# DCDC-17VXV5A.net
KiCad netlist of a schematic drawn in EAGLE
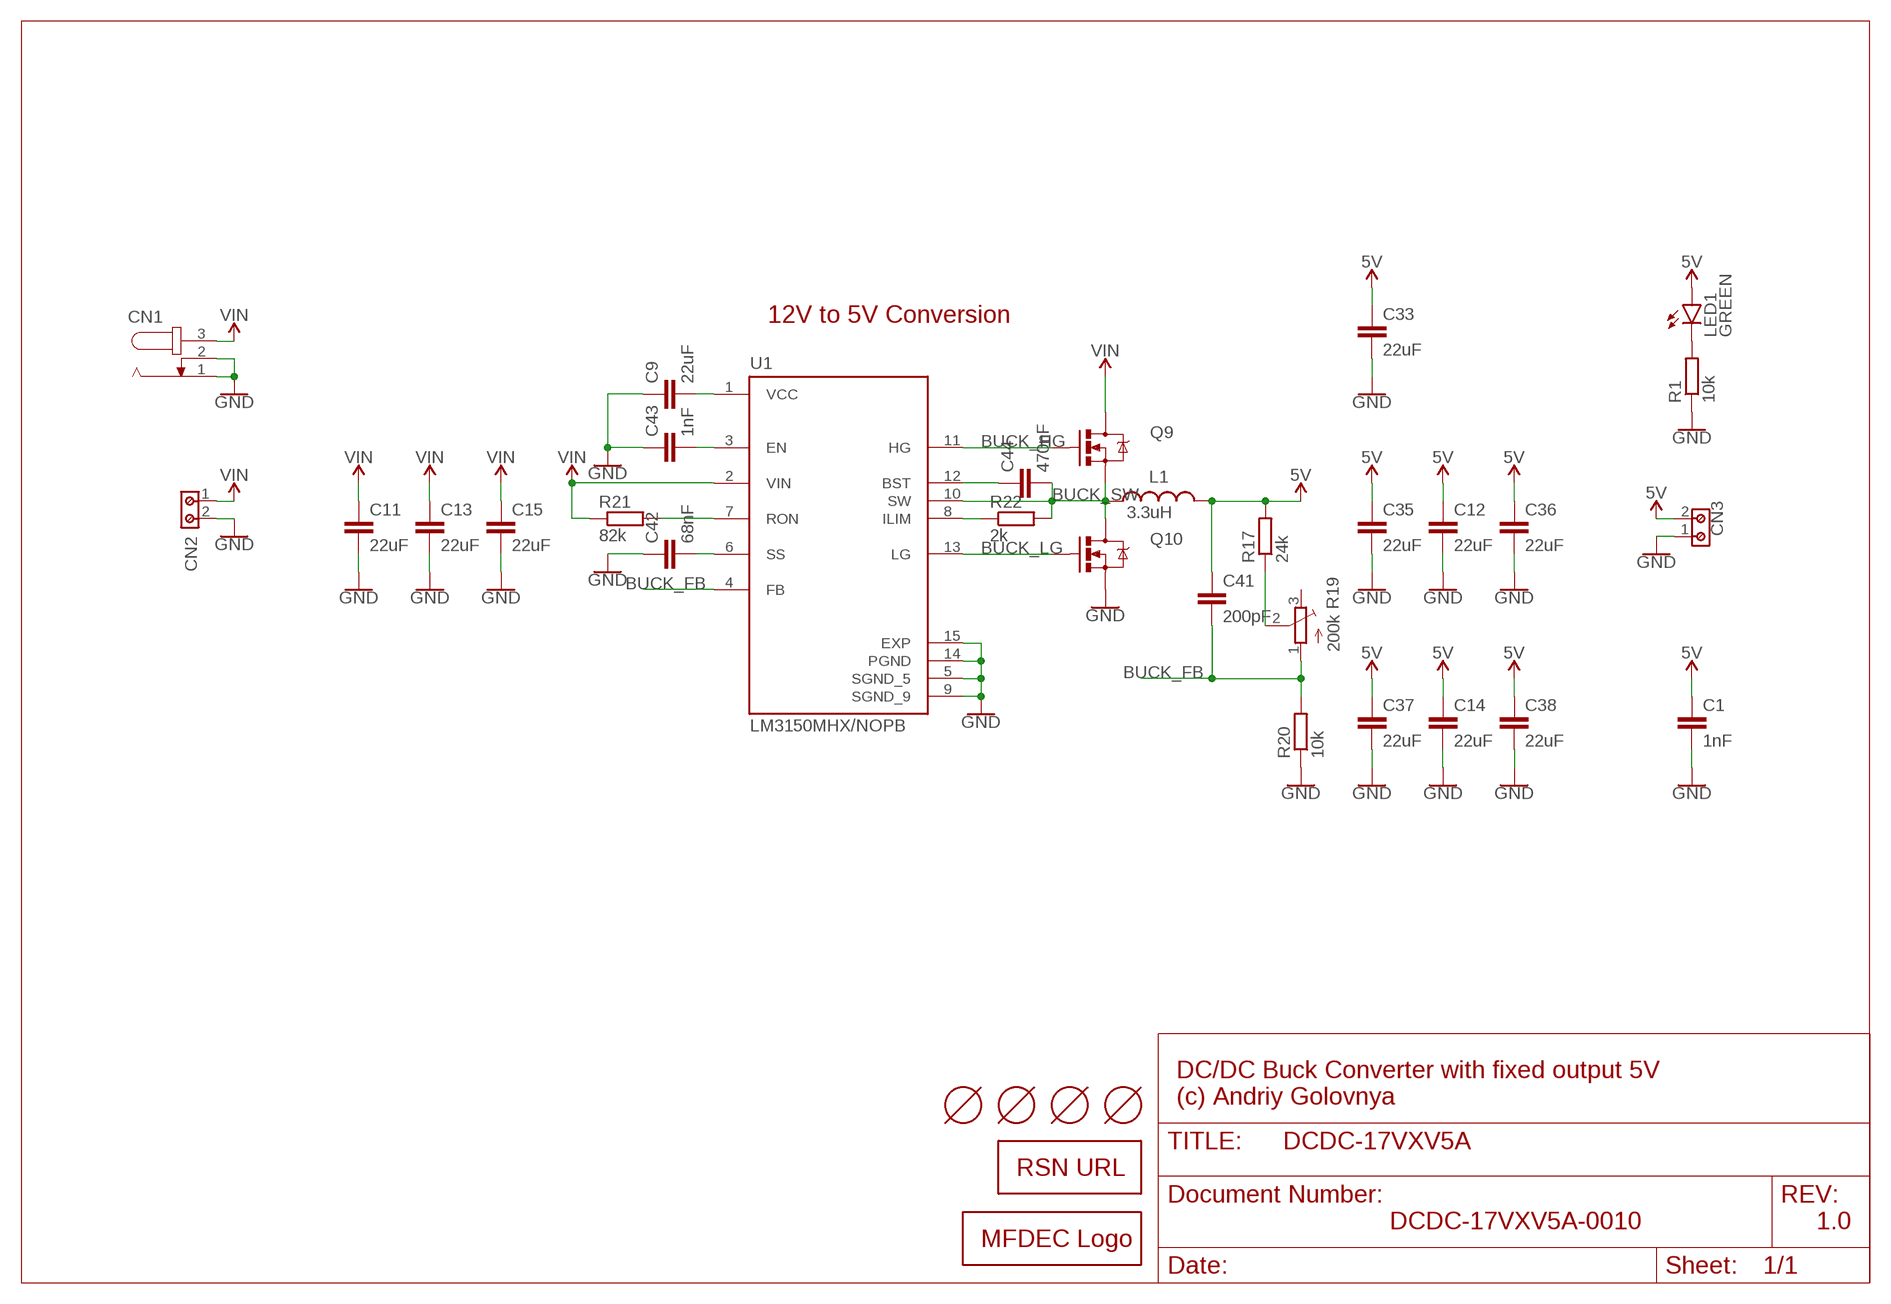
[diagram p0: schematic, sheet 1]

(export (version "E")
  (design (tool "Eeschema 10.0.6"))
  (components
    (comp (ref "C1")
      (value "1nF")
      (footprint "eagle-import:C0603K")
      (libsource (lib "eagle-import") (part "C-EUC0603K"))
    )
    (comp (ref "C9")
      (value "22uF")
      (footprint "eagle-import:C0805K")
      (libsource (lib "eagle-import") (part "C-EUC0805K"))
    )
    (comp (ref "C11")
      (value "22uF")
      (footprint "eagle-import:C0805K")
      (libsource (lib "eagle-import") (part "C-EUC0805K"))
    )
    (comp (ref "C12")
      (value "22uF")
      (footprint "eagle-import:C0805K")
      (libsource (lib "eagle-import") (part "C-EUC0805K"))
    )
    (comp (ref "C13")
      (value "22uF")
      (footprint "eagle-import:C0805K")
      (libsource (lib "eagle-import") (part "C-EUC0805K"))
    )
    (comp (ref "C14")
      (value "22uF")
      (footprint "eagle-import:C0805K")
      (libsource (lib "eagle-import") (part "C-EUC0805K"))
    )
    (comp (ref "C15")
      (value "22uF")
      (footprint "eagle-import:C0805K")
      (libsource (lib "eagle-import") (part "C-EUC0805K"))
    )
    (comp (ref "C33")
      (value "22uF")
      (footprint "eagle-import:C0805K")
      (libsource (lib "eagle-import") (part "C-EUC0805K"))
    )
    (comp (ref "C35")
      (value "22uF")
      (footprint "eagle-import:C0805K")
      (libsource (lib "eagle-import") (part "C-EUC0805K"))
    )
    (comp (ref "C36")
      (value "22uF")
      (footprint "eagle-import:C0805K")
      (libsource (lib "eagle-import") (part "C-EUC0805K"))
    )
    (comp (ref "C37")
      (value "22uF")
      (footprint "eagle-import:C0805K")
      (libsource (lib "eagle-import") (part "C-EUC0805K"))
    )
    (comp (ref "C38")
      (value "22uF")
      (footprint "eagle-import:C0805K")
      (libsource (lib "eagle-import") (part "C-EUC0805K"))
    )
    (comp (ref "C41")
      (value "200pF")
      (footprint "eagle-import:C0603K")
      (libsource (lib "eagle-import") (part "C-EUC0603K"))
    )
    (comp (ref "C42")
      (value "68nF")
      (footprint "eagle-import:C0603K")
      (libsource (lib "eagle-import") (part "C-EUC0603K"))
    )
    (comp (ref "C43")
      (value "1nF")
      (footprint "eagle-import:C0603K")
      (libsource (lib "eagle-import") (part "C-EUC0603K"))
    )
    (comp (ref "C44")
      (value "470nF")
      (footprint "eagle-import:C0603K")
      (libsource (lib "eagle-import") (part "C-EUC0603K"))
    )
    (comp (ref "CN1")
      (value "JACK-PLUG1")
      (footprint "eagle-import:SPC4078")
      (libsource (lib "eagle-import") (part "JACK-PLUG1"))
    )
    (comp (ref "CN2")
      (value "691213510002")
      (footprint "eagle-import:691213510002")
      (libsource (lib "eagle-import") (part "691213510002"))
    )
    (comp (ref "CN3")
      (value "691213510002")
      (footprint "eagle-import:691213510002")
      (libsource (lib "eagle-import") (part "691213510002"))
    )
    (comp (ref "HOLE1")
      (value "TOOLINGHOLE")
      (footprint "eagle-import:TOOLING-HOLE")
      (libsource (lib "eagle-import") (part "TOOLINGHOLE"))
    )
    (comp (ref "HOLE2")
      (value "TOOLINGHOLE")
      (footprint "eagle-import:TOOLING-HOLE")
      (libsource (lib "eagle-import") (part "TOOLINGHOLE"))
    )
    (comp (ref "HOLE3")
      (value "TOOLINGHOLE")
      (footprint "eagle-import:TOOLING-HOLE")
      (libsource (lib "eagle-import") (part "TOOLINGHOLE"))
    )
    (comp (ref "HOLE4")
      (value "TOOLINGHOLE")
      (footprint "eagle-import:TOOLING-HOLE")
      (libsource (lib "eagle-import") (part "TOOLINGHOLE"))
    )
    (comp (ref "L1")
      (value "3.3uH")
      (footprint "eagle-import:WE-CHSA_1011")
      (libsource (lib "eagle-import") (part "WE-CHSA_1011_7843330330"))
    )
    (comp (ref "LED1")
      (value "GREEN")
      (footprint "eagle-import:SML0603")
      (libsource (lib "eagle-import") (part "LEDSML0603"))
    )
    (comp (ref "LOGO1")
      (value "RSNURL_QR_8MM")
      (footprint "eagle-import:RSNURL_QR_8MM")
      (libsource (lib "eagle-import") (part "RSNURL_QR_8MM"))
    )
    (comp (ref "LOGO2")
      (value "MFDECLOGO_L_10MM")
      (footprint "eagle-import:MFDEC_L_10MM")
      (libsource (lib "eagle-import") (part "MFDECLOGO_L_10MM"))
    )
    (comp (ref "Q9")
      (value "NMOSFET")
      (footprint "eagle-import:DPAK")
      (libsource (lib "eagle-import") (part "MOSFET-NCHANNELFDD8780"))
    )
    (comp (ref "Q10")
      (value "NMOSFET")
      (footprint "eagle-import:DPAK")
      (libsource (lib "eagle-import") (part "MOSFET-NCHANNELFDD8780"))
    )
    (comp (ref "R1")
      (value "10k")
      (footprint "eagle-import:R0603")
      (libsource (lib "eagle-import") (part "R-EU_R0603"))
    )
    (comp (ref "R17")
      (value "24k")
      (footprint "eagle-import:R0603")
      (libsource (lib "eagle-import") (part "R-EU_R0603"))
    )
    (comp (ref "R19")
      (value "200k")
      (footprint "eagle-import:TC33X")
      (libsource (lib "eagle-import") (part "TRIMPOTTC33X"))
    )
    (comp (ref "R20")
      (value "10k")
      (footprint "eagle-import:R0603")
      (libsource (lib "eagle-import") (part "R-EU_R0603"))
    )
    (comp (ref "R21")
      (value "82k")
      (footprint "eagle-import:R0603")
      (libsource (lib "eagle-import") (part "R-EU_R0603"))
    )
    (comp (ref "R22")
      (value "2k")
      (footprint "eagle-import:R0603")
      (libsource (lib "eagle-import") (part "R-EU_R0603"))
    )
    (comp (ref "U1")
      (value "LM3150MHX/NOPB")
      (footprint "eagle-import:SOP65P640X110-15N")
      (fields (field (name "MF") "Texas Instruments"))
      (libsource (lib "eagle-import") (part "LM3150MHX/NOPB"))
    )
  )
  (nets
    (net (code "1") (name "/BUCK_FB") (class "Default")
      (node (ref "C41") (pin "2") (pinfunction "2_2") (pintype "passive"))
      (node (ref "R19") (pin "1") (pinfunction "A_1") (pintype "passive"))
      (node (ref "R20") (pin "2") (pinfunction "2_2") (pintype "passive"))
      (node (ref "U1") (pin "4") (pinfunction "FB_4") (pintype "input"))
    )
    (net (code "2") (name "/BUCK_HG") (class "Default")
      (node (ref "Q9") (pin "1") (pinfunction "G_1") (pintype "passive"))
      (node (ref "U1") (pin "11") (pinfunction "HG_11") (pintype "output"))
    )
    (net (code "3") (name "/BUCK_LG") (class "Default")
      (node (ref "Q10") (pin "1") (pinfunction "G_1") (pintype "passive"))
      (node (ref "U1") (pin "13") (pinfunction "LG_13") (pintype "output"))
    )
    (net (code "4") (name "/BUCK_SW") (class "Default")
      (node (ref "C44") (pin "2") (pinfunction "2_2") (pintype "passive"))
      (node (ref "L1") (pin "1") (pinfunction "1_1") (pintype "passive"))
      (node (ref "Q10") (pin "4") (pinfunction "D_4") (pintype "passive"))
      (node (ref "Q9") (pin "3") (pinfunction "S_3") (pintype "passive"))
      (node (ref "R22") (pin "2") (pinfunction "2_2") (pintype "passive"))
      (node (ref "U1") (pin "10") (pinfunction "SW_10") (pintype "output"))
    )
    (net (code "5") (name "5V") (class "Default")
      (node (ref "C1") (pin "1") (pinfunction "1_1") (pintype "passive"))
      (node (ref "C12") (pin "1") (pinfunction "1_1") (pintype "passive"))
      (node (ref "C14") (pin "1") (pinfunction "1_1") (pintype "passive"))
      (node (ref "C33") (pin "1") (pinfunction "1_1") (pintype "passive"))
      (node (ref "C35") (pin "1") (pinfunction "1_1") (pintype "passive"))
      (node (ref "C36") (pin "1") (pinfunction "1_1") (pintype "passive"))
      (node (ref "C37") (pin "1") (pinfunction "1_1") (pintype "passive"))
      (node (ref "C38") (pin "1") (pinfunction "1_1") (pintype "passive"))
      (node (ref "C41") (pin "1") (pinfunction "1_1") (pintype "passive"))
      (node (ref "CN3") (pin "2") (pinfunction "2_2") (pintype "passive"))
      (node (ref "L1") (pin "2") (pinfunction "2_2") (pintype "passive"))
      (node (ref "LED1") (pin "A") (pinfunction "A_A") (pintype "passive"))
      (node (ref "R17") (pin "2") (pinfunction "2_2") (pintype "passive"))
    )
    (net (code "6") (name "GND") (class "Default")
      (node (ref "C1") (pin "2") (pinfunction "2_2") (pintype "passive"))
      (node (ref "C11") (pin "2") (pinfunction "2_2") (pintype "passive"))
      (node (ref "C12") (pin "2") (pinfunction "2_2") (pintype "passive"))
      (node (ref "C13") (pin "2") (pinfunction "2_2") (pintype "passive"))
      (node (ref "C14") (pin "2") (pinfunction "2_2") (pintype "passive"))
      (node (ref "C15") (pin "2") (pinfunction "2_2") (pintype "passive"))
      (node (ref "C33") (pin "2") (pinfunction "2_2") (pintype "passive"))
      (node (ref "C35") (pin "2") (pinfunction "2_2") (pintype "passive"))
      (node (ref "C36") (pin "2") (pinfunction "2_2") (pintype "passive"))
      (node (ref "C37") (pin "2") (pinfunction "2_2") (pintype "passive"))
      (node (ref "C38") (pin "2") (pinfunction "2_2") (pintype "passive"))
      (node (ref "C42") (pin "1") (pinfunction "1_1") (pintype "passive"))
      (node (ref "C43") (pin "1") (pinfunction "1_1") (pintype "passive"))
      (node (ref "C9") (pin "1") (pinfunction "1_1") (pintype "passive"))
      (node (ref "CN1") (pin "1") (pinfunction "1_1") (pintype "passive"))
      (node (ref "CN1") (pin "2") (pinfunction "2_2") (pintype "passive"))
      (node (ref "CN2") (pin "2") (pinfunction "2_2") (pintype "passive"))
      (node (ref "CN3") (pin "1") (pinfunction "1_1") (pintype "passive"))
      (node (ref "Q10") (pin "3") (pinfunction "S_3") (pintype "passive"))
      (node (ref "R1") (pin "1") (pinfunction "1_1") (pintype "passive"))
      (node (ref "R20") (pin "1") (pinfunction "1_1") (pintype "passive"))
      (node (ref "U1") (pin "14") (pinfunction "PGND_14") (pintype "power_in"))
      (node (ref "U1") (pin "15") (pinfunction "EXP_15") (pintype "power_in"))
      (node (ref "U1") (pin "5") (pinfunction "SGND_5_5") (pintype "power_in"))
      (node (ref "U1") (pin "9") (pinfunction "SGND_9_9") (pintype "power_in"))
    )
    (net (code "7") (name "Net-(LED1-PadC)") (class "Default")
      (node (ref "LED1") (pin "C") (pinfunction "C_C") (pintype "passive"))
      (node (ref "R1") (pin "2") (pinfunction "2_2") (pintype "passive"))
    )
    (net (code "8") (name "Net-(R19-S)") (class "Default")
      (node (ref "R17") (pin "1") (pinfunction "1_1") (pintype "passive"))
      (node (ref "R19") (pin "2") (pinfunction "S_2") (pintype "passive"))
    )
    (net (code "9") (name "Net-(U1-BST)") (class "Default")
      (node (ref "C44") (pin "1") (pinfunction "1_1") (pintype "passive"))
      (node (ref "U1") (pin "12") (pinfunction "BST_12") (pintype "passive"))
    )
    (net (code "10") (name "Net-(U1-EN)") (class "Default")
      (node (ref "C43") (pin "2") (pinfunction "2_2") (pintype "passive"))
      (node (ref "U1") (pin "3") (pinfunction "EN_3") (pintype "input"))
    )
    (net (code "11") (name "Net-(U1-ILIM)") (class "Default")
      (node (ref "R22") (pin "1") (pinfunction "1_1") (pintype "passive"))
      (node (ref "U1") (pin "8") (pinfunction "ILIM_8") (pintype "passive"))
    )
    (net (code "12") (name "Net-(U1-RON)") (class "Default")
      (node (ref "R21") (pin "2") (pinfunction "2_2") (pintype "passive"))
      (node (ref "U1") (pin "7") (pinfunction "RON_7") (pintype "input"))
    )
    (net (code "13") (name "Net-(U1-SS)") (class "Default")
      (node (ref "C42") (pin "2") (pinfunction "2_2") (pintype "passive"))
      (node (ref "U1") (pin "6") (pinfunction "SS_6") (pintype "input"))
    )
    (net (code "14") (name "Net-(U1-VCC)") (class "Default")
      (node (ref "C9") (pin "2") (pinfunction "2_2") (pintype "passive"))
      (node (ref "U1") (pin "1") (pinfunction "VCC_1") (pintype "power_in"))
    )
    (net (code "15") (name "VIN") (class "Default")
      (node (ref "C11") (pin "1") (pinfunction "1_1") (pintype "passive"))
      (node (ref "C13") (pin "1") (pinfunction "1_1") (pintype "passive"))
      (node (ref "C15") (pin "1") (pinfunction "1_1") (pintype "passive"))
      (node (ref "CN1") (pin "3") (pinfunction "3_3") (pintype "passive"))
      (node (ref "CN2") (pin "1") (pinfunction "1_1") (pintype "passive"))
      (node (ref "Q9") (pin "4") (pinfunction "D_4") (pintype "passive"))
      (node (ref "R21") (pin "1") (pinfunction "1_1") (pintype "passive"))
      (node (ref "U1") (pin "2") (pinfunction "VIN_2") (pintype "input"))
    )
    (net (code "16") (name "unconnected-(R19-E-Pad3)") (class "Default")
      (node (ref "R19") (pin "3") (pinfunction "E_3") (pintype "passive"))
    )
  )
)
